# Sampling_Board.net
KiCad netlist of a schematic drawn in Altium Designer
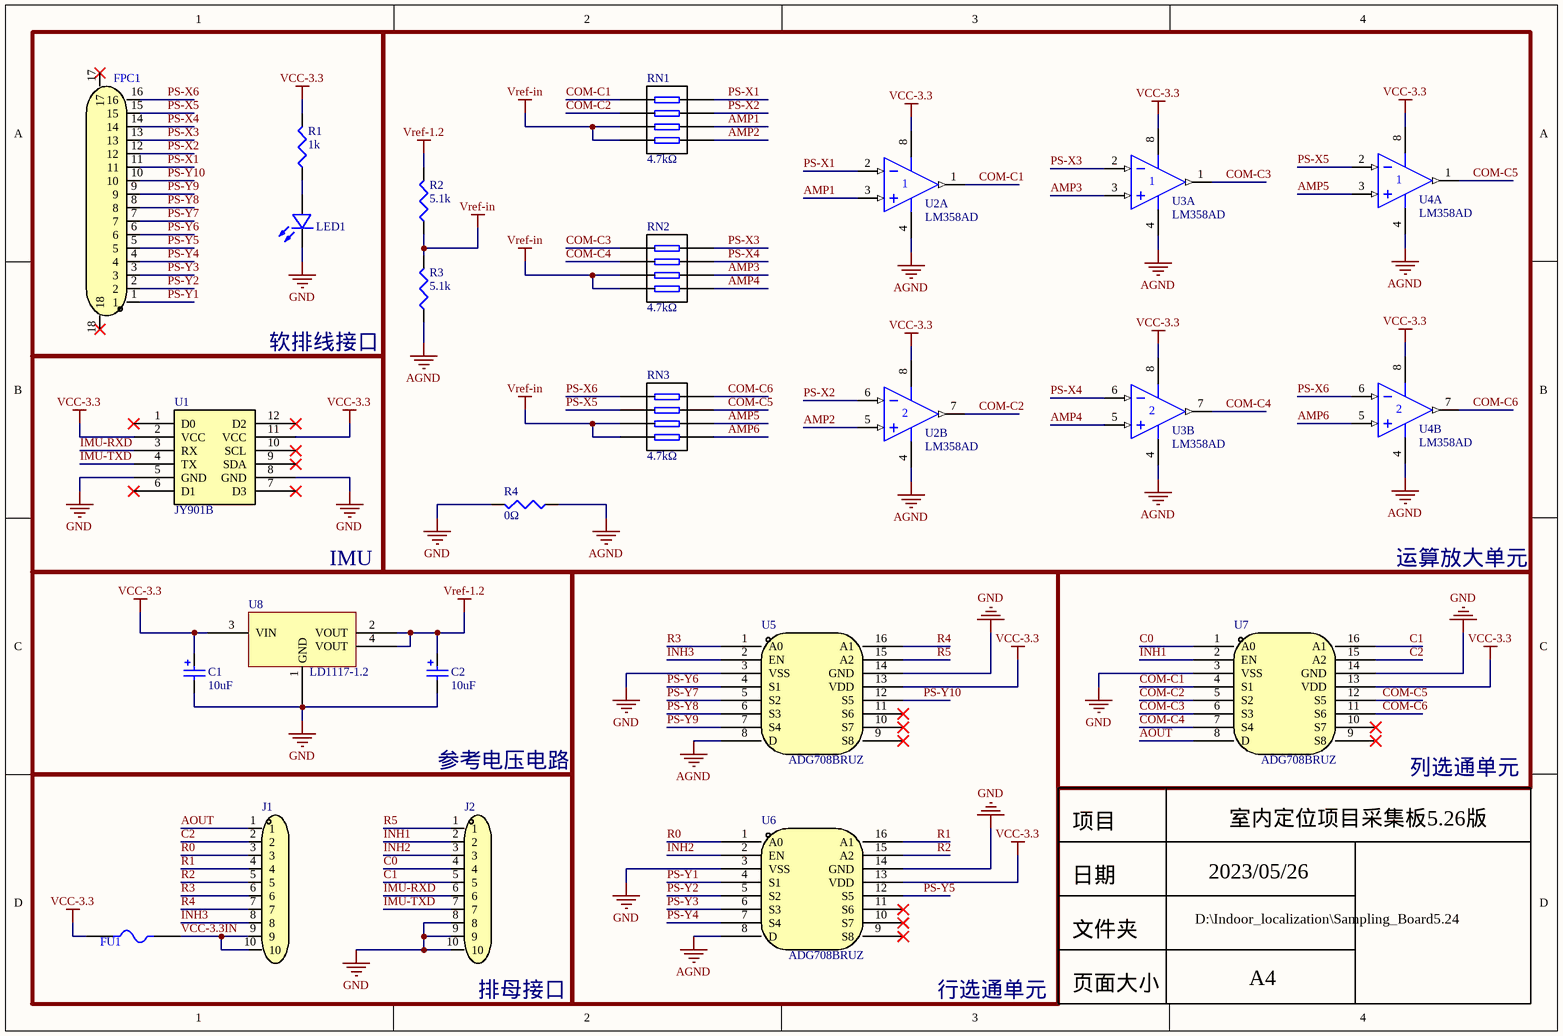
[diagram p0: Sampling_Board.SchDoc]

(export (version "E")
  (design (tool "Eeschema 10.0.6"))
  (components
    (comp (ref "C1")
      (value "10uF")
      (footprint "CAP-SMD_L3.2-W1.6-RD-C7171")
      (description "贴片钽电容")
      (fields (field (name "MANUFACTURER") "Kyocera AVX") (field (name "MANUFACTURER PART") "TAJA106K016RNJ"))
      (libsource (lib "Passive_Device") (part "Cap-TAJA"))
    )
    (comp (ref "C2")
      (value "10uF")
      (footprint "CAP-SMD_L3.2-W1.6-RD-C7171")
      (description "贴片钽电容")
      (fields (field (name "MANUFACTURER") "Kyocera AVX") (field (name "MANUFACTURER PART") "TAJA106K016RNJ"))
      (libsource (lib "Passive_Device") (part "Cap-TAJA"))
    )
    (comp (ref "FPC1")
      (value "1.0K-DX-16PWB")
      (footprint "FPC-SMD_16P-P1.00_HDGC_1.0K-DX-16PWB")
      (description "软排线接口16P")
      (fields (field (name "MANUFACTURER") "HDGC(华德共创)"))
      (libsource (lib "Connector") (part "FPC16P"))
    )
    (comp (ref "FU1")
      (value "FUSE 1A")
      (footprint "F0805")
      (description "贴片保险丝")
      (fields (field (name "MANUFACTURER") "RUILON(瑞隆源)") (field (name "MANUFACTURER PART") "SMD0805P075TF"))
      (libsource (lib "Passive_Device") (part "FU"))
    )
    (comp (ref "J1")
      (value "Header 10X1")
      (footprint "HDR-TH_10P-P2.54_MF254V-11-10-0743")
      (description "10P*1接插件")
      (fields (field (name "DESIGNER") "U?"))
      (libsource (lib "Connector") (part "Header 10X1"))
    )
    (comp (ref "J2")
      (value "Header 10X1")
      (footprint "HDR-TH_10P-P2.54_MF254V-11-10-0743")
      (description "10P*1接插件")
      (fields (field (name "DESIGNER") "U?"))
      (libsource (lib "Connector") (part "Header 10X1"))
    )
    (comp (ref "LED1")
      (value "NCD0603G2")
      (footprint "LED0603-RD")
      (description "LED")
      (fields (field (name "MANUFACTURER") "国星光电"))
      (libsource (lib "Component") (part "NCD0603G2"))
    )
    (comp (ref "R1")
      (value "1k")
      (footprint "R0603")
      (description "Resistor")
      (fields (field (name "PUBLISHER") "Altium Limited"))
      (libsource (lib "Miscellaneous Devices") (part "Res3"))
    )
    (comp (ref "R2")
      (value "5.1k")
      (footprint "R0603")
      (description "Resistor")
      (fields (field (name "PUBLISHER") "Altium Limited"))
      (libsource (lib "Miscellaneous Devices") (part "Res3"))
    )
    (comp (ref "R3")
      (value "5.1k")
      (footprint "R0603")
      (description "Resistor")
      (fields (field (name "PUBLISHER") "Altium Limited"))
      (libsource (lib "Miscellaneous Devices") (part "Res3"))
    )
    (comp (ref "R4")
      (value "0Ω")
      (footprint "R0603")
      (description "Resistor")
      (fields (field (name "PUBLISHER") "Altium Limited"))
      (libsource (lib "Miscellaneous Devices") (part "Res3"))
    )
    (comp (ref "RN1")
      (value "4.7kΩ")
      (footprint "RES-ARRAY-SMD_0603-8P-L3.2-W1.6-BL")
      (description "贴片排阻*4")
      (fields (field (name "MANUFACTURER") "FH(风华)") (field (name "MANUFACTURER PART") "RC-ML08W103JT"))
      (libsource (lib "Passive_Device") (part "Res*4"))
    )
    (comp (ref "RN2")
      (value "4.7kΩ")
      (footprint "RES-ARRAY-SMD_0603-8P-L3.2-W1.6-BL")
      (description "贴片排阻*4")
      (fields (field (name "MANUFACTURER") "FH(风华)") (field (name "MANUFACTURER PART") "RC-ML08W103JT"))
      (libsource (lib "Passive_Device") (part "Res*4"))
    )
    (comp (ref "RN3")
      (value "4.7kΩ")
      (footprint "RES-ARRAY-SMD_0603-8P-L3.2-W1.6-BL")
      (description "贴片排阻*4")
      (fields (field (name "MANUFACTURER") "FH(风华)") (field (name "MANUFACTURER PART") "RC-ML08W103JT"))
      (libsource (lib "Passive_Device") (part "Res*4"))
    )
    (comp (ref "U1")
      (value "JY901B")
      (footprint "JY901B")
      (description "Ten axis inertial sensor")
      (libsource (lib "IMU") (part "JY901B"))
    )
    (comp (ref "U2")
      (value "LM358AD")
      (footprint "D008_L")
      (description "Dual Operational Amplifier")
      (fields (field (name "PUBLISHER") "Altium Limited"))
      (libsource (lib "TI Operational Amplifier") (part "LM358AD"))
    )
    (comp (ref "U3")
      (value "LM358AD")
      (footprint "D008_L")
      (description "Dual Operational Amplifier")
      (fields (field (name "PUBLISHER") "Altium Limited"))
      (libsource (lib "TI Operational Amplifier") (part "LM358AD"))
    )
    (comp (ref "U4")
      (value "LM358AD")
      (footprint "D008_L")
      (description "Dual Operational Amplifier")
      (fields (field (name "PUBLISHER") "Altium Limited"))
      (libsource (lib "TI Operational Amplifier") (part "LM358AD"))
    )
    (comp (ref "U5")
      (value "ADG708BRUZ")
      (footprint "TSSOP-16_L5.0-W4.4-P0.65-LS6.4-BL")
      (description "低电压8通道多路复用器")
      (fields (field (name "MANUFACTURER") "ADI(亚德诺)/LINEAR(凌特)"))
      (libsource (lib "IC_Device") (part "ADG708BRUZ"))
    )
    (comp (ref "U6")
      (value "ADG708BRUZ")
      (footprint "TSSOP-16_L5.0-W4.4-P0.65-LS6.4-BL")
      (description "低电压8通道多路复用器")
      (fields (field (name "MANUFACTURER") "ADI(亚德诺)/LINEAR(凌特)"))
      (libsource (lib "IC_Device") (part "ADG708BRUZ"))
    )
    (comp (ref "U7")
      (value "ADG708BRUZ")
      (footprint "TSSOP-16_L5.0-W4.4-P0.65-LS6.4-BL")
      (description "低电压8通道多路复用器")
      (fields (field (name "MANUFACTURER") "ADI(亚德诺)/LINEAR(凌特)"))
      (libsource (lib "IC_Device") (part "ADG708BRUZ"))
    )
    (comp (ref "U8")
      (value "LD1117-1.2")
      (footprint "SOT-223-3_L6.5-W3.4-P2.30-LS7.0-BR")
      (description "低压差线性稳压器1.2V")
      (libsource (lib "Power") (part "LD1117-1.2"))
    )
  )
  (nets
    (net (code "2") (name "/AMP1") (class "Default")
      (node (ref "RN1") (pin "2") (pinfunction "2_2") (pintype "passive"))
      (node (ref "U2") (pin "3") (pinfunction "IN+_3") (pintype "input"))
    )
    (net (code "3") (name "/AMP2") (class "Default")
      (node (ref "RN1") (pin "1") (pinfunction "1_1") (pintype "passive"))
      (node (ref "U2") (pin "5") (pinfunction "IN+_5") (pintype "input"))
    )
    (net (code "4") (name "/AMP3") (class "Default")
      (node (ref "RN2") (pin "2") (pinfunction "2_2") (pintype "passive"))
      (node (ref "U3") (pin "3") (pinfunction "IN+_3") (pintype "input"))
    )
    (net (code "5") (name "/AMP4") (class "Default")
      (node (ref "RN2") (pin "1") (pinfunction "1_1") (pintype "passive"))
      (node (ref "U3") (pin "5") (pinfunction "IN+_5") (pintype "input"))
    )
    (net (code "6") (name "/AMP5") (class "Default")
      (node (ref "RN3") (pin "2") (pinfunction "2_2") (pintype "passive"))
      (node (ref "U4") (pin "3") (pinfunction "IN+_3") (pintype "input"))
    )
    (net (code "7") (name "/AMP6") (class "Default")
      (node (ref "RN3") (pin "1") (pinfunction "1_1") (pintype "passive"))
      (node (ref "U4") (pin "5") (pinfunction "IN+_5") (pintype "input"))
    )
    (net (code "8") (name "/AOUT") (class "Default")
      (node (ref "J1") (pin "1") (pinfunction "1_1") (pintype "passive"))
      (node (ref "U7") (pin "8") (pinfunction "D_8") (pintype "passive"))
    )
    (net (code "9") (name "/C0") (class "Default")
      (node (ref "J2") (pin "4") (pinfunction "4_4") (pintype "passive"))
      (node (ref "U7") (pin "1") (pinfunction "A0_1") (pintype "passive"))
    )
    (net (code "10") (name "/C1") (class "Default")
      (node (ref "J2") (pin "5") (pinfunction "5_5") (pintype "passive"))
      (node (ref "U7") (pin "16") (pinfunction "A1_16") (pintype "passive"))
    )
    (net (code "11") (name "/C2") (class "Default")
      (node (ref "J1") (pin "2") (pinfunction "2_2") (pintype "passive"))
      (node (ref "U7") (pin "15") (pinfunction "A2_15") (pintype "passive"))
    )
    (net (code "12") (name "/COM-C1") (class "Default")
      (node (ref "RN1") (pin "5") (pinfunction "5_5") (pintype "passive"))
      (node (ref "U2") (pin "1") (pinfunction "OUT_1") (pintype "output"))
      (node (ref "U7") (pin "4") (pinfunction "S1_4") (pintype "passive"))
    )
    (net (code "13") (name "/COM-C2") (class "Default")
      (node (ref "RN1") (pin "6") (pinfunction "6_6") (pintype "passive"))
      (node (ref "U2") (pin "7") (pinfunction "OUT_7") (pintype "output"))
      (node (ref "U7") (pin "5") (pinfunction "S2_5") (pintype "passive"))
    )
    (net (code "14") (name "/COM-C3") (class "Default")
      (node (ref "RN2") (pin "5") (pinfunction "5_5") (pintype "passive"))
      (node (ref "U3") (pin "1") (pinfunction "OUT_1") (pintype "output"))
      (node (ref "U7") (pin "6") (pinfunction "S3_6") (pintype "passive"))
    )
    (net (code "15") (name "/COM-C4") (class "Default")
      (node (ref "RN2") (pin "6") (pinfunction "6_6") (pintype "passive"))
      (node (ref "U3") (pin "7") (pinfunction "OUT_7") (pintype "output"))
      (node (ref "U7") (pin "7") (pinfunction "S4_7") (pintype "passive"))
    )
    (net (code "16") (name "/COM-C5") (class "Default")
      (node (ref "RN3") (pin "3") (pinfunction "3_3") (pintype "passive"))
      (node (ref "U4") (pin "1") (pinfunction "OUT_1") (pintype "output"))
      (node (ref "U7") (pin "12") (pinfunction "S5_12") (pintype "passive"))
    )
    (net (code "17") (name "/COM-C6") (class "Default")
      (node (ref "RN3") (pin "4") (pinfunction "4_4") (pintype "passive"))
      (node (ref "U4") (pin "7") (pinfunction "OUT_7") (pintype "output"))
      (node (ref "U7") (pin "11") (pinfunction "S6_11") (pintype "passive"))
    )
    (net (code "18") (name "/IMU-RXD") (class "Default")
      (node (ref "J2") (pin "6") (pinfunction "6_6") (pintype "passive"))
      (node (ref "U1") (pin "3") (pinfunction "RX_3") (pintype "passive"))
    )
    (net (code "19") (name "/IMU-TXD") (class "Default")
      (node (ref "J2") (pin "7") (pinfunction "7_7") (pintype "passive"))
      (node (ref "U1") (pin "4") (pinfunction "TX_4") (pintype "passive"))
    )
    (net (code "20") (name "/INH1") (class "Default")
      (node (ref "J2") (pin "2") (pinfunction "2_2") (pintype "passive"))
      (node (ref "U7") (pin "2") (pinfunction "EN_2") (pintype "passive"))
    )
    (net (code "21") (name "/INH2") (class "Default")
      (node (ref "J2") (pin "3") (pinfunction "3_3") (pintype "passive"))
      (node (ref "U6") (pin "2") (pinfunction "EN_2") (pintype "passive"))
    )
    (net (code "22") (name "/INH3") (class "Default")
      (node (ref "J1") (pin "8") (pinfunction "8_8") (pintype "passive"))
      (node (ref "U5") (pin "2") (pinfunction "EN_2") (pintype "passive"))
    )
    (net (code "23") (name "/PS-X1") (class "Default")
      (node (ref "FPC1") (pin "11") (pinfunction "11_11") (pintype "passive"))
      (node (ref "RN1") (pin "4") (pinfunction "4_4") (pintype "passive"))
      (node (ref "U2") (pin "2") (pinfunction "IN-_2") (pintype "input"))
    )
    (net (code "24") (name "/PS-X2") (class "Default")
      (node (ref "FPC1") (pin "12") (pinfunction "12_12") (pintype "passive"))
      (node (ref "RN1") (pin "3") (pinfunction "3_3") (pintype "passive"))
      (node (ref "U2") (pin "6") (pinfunction "IN-_6") (pintype "input"))
    )
    (net (code "25") (name "/PS-X3") (class "Default")
      (node (ref "FPC1") (pin "13") (pinfunction "13_13") (pintype "passive"))
      (node (ref "RN2") (pin "4") (pinfunction "4_4") (pintype "passive"))
      (node (ref "U3") (pin "2") (pinfunction "IN-_2") (pintype "input"))
    )
    (net (code "26") (name "/PS-X4") (class "Default")
      (node (ref "FPC1") (pin "14") (pinfunction "14_14") (pintype "passive"))
      (node (ref "RN2") (pin "3") (pinfunction "3_3") (pintype "passive"))
      (node (ref "U3") (pin "6") (pinfunction "IN-_6") (pintype "input"))
    )
    (net (code "27") (name "/PS-X5") (class "Default")
      (node (ref "FPC1") (pin "15") (pinfunction "15_15") (pintype "passive"))
      (node (ref "RN3") (pin "6") (pinfunction "6_6") (pintype "passive"))
      (node (ref "U4") (pin "2") (pinfunction "IN-_2") (pintype "input"))
    )
    (net (code "28") (name "/PS-X6") (class "Default")
      (node (ref "FPC1") (pin "16") (pinfunction "16_16") (pintype "passive"))
      (node (ref "RN3") (pin "5") (pinfunction "5_5") (pintype "passive"))
      (node (ref "U4") (pin "6") (pinfunction "IN-_6") (pintype "input"))
    )
    (net (code "29") (name "/PS-Y1") (class "Default")
      (node (ref "FPC1") (pin "1") (pinfunction "1_1") (pintype "passive"))
      (node (ref "U6") (pin "4") (pinfunction "S1_4") (pintype "passive"))
    )
    (net (code "30") (name "/PS-Y2") (class "Default")
      (node (ref "FPC1") (pin "2") (pinfunction "2_2") (pintype "passive"))
      (node (ref "U6") (pin "5") (pinfunction "S2_5") (pintype "passive"))
    )
    (net (code "31") (name "/PS-Y3") (class "Default")
      (node (ref "FPC1") (pin "3") (pinfunction "3_3") (pintype "passive"))
      (node (ref "U6") (pin "6") (pinfunction "S3_6") (pintype "passive"))
    )
    (net (code "32") (name "/PS-Y4") (class "Default")
      (node (ref "FPC1") (pin "4") (pinfunction "4_4") (pintype "passive"))
      (node (ref "U6") (pin "7") (pinfunction "S4_7") (pintype "passive"))
    )
    (net (code "33") (name "/PS-Y5") (class "Default")
      (node (ref "FPC1") (pin "5") (pinfunction "5_5") (pintype "passive"))
      (node (ref "U6") (pin "12") (pinfunction "S5_12") (pintype "passive"))
    )
    (net (code "34") (name "/PS-Y6") (class "Default")
      (node (ref "FPC1") (pin "6") (pinfunction "6_6") (pintype "passive"))
      (node (ref "U5") (pin "4") (pinfunction "S1_4") (pintype "passive"))
    )
    (net (code "35") (name "/PS-Y7") (class "Default")
      (node (ref "FPC1") (pin "7") (pinfunction "7_7") (pintype "passive"))
      (node (ref "U5") (pin "5") (pinfunction "S2_5") (pintype "passive"))
    )
    (net (code "36") (name "/PS-Y8") (class "Default")
      (node (ref "FPC1") (pin "8") (pinfunction "8_8") (pintype "passive"))
      (node (ref "U5") (pin "6") (pinfunction "S3_6") (pintype "passive"))
    )
    (net (code "37") (name "/PS-Y9") (class "Default")
      (node (ref "FPC1") (pin "9") (pinfunction "9_9") (pintype "passive"))
      (node (ref "U5") (pin "7") (pinfunction "S4_7") (pintype "passive"))
    )
    (net (code "38") (name "/PS-Y10") (class "Default")
      (node (ref "FPC1") (pin "10") (pinfunction "10_10") (pintype "passive"))
      (node (ref "U5") (pin "12") (pinfunction "S5_12") (pintype "passive"))
    )
    (net (code "39") (name "/R0") (class "Default")
      (node (ref "J1") (pin "3") (pinfunction "3_3") (pintype "passive"))
      (node (ref "U6") (pin "1") (pinfunction "A0_1") (pintype "passive"))
    )
    (net (code "40") (name "/R1") (class "Default")
      (node (ref "J1") (pin "4") (pinfunction "4_4") (pintype "passive"))
      (node (ref "U6") (pin "16") (pinfunction "A1_16") (pintype "passive"))
    )
    (net (code "41") (name "/R2") (class "Default")
      (node (ref "J1") (pin "5") (pinfunction "5_5") (pintype "passive"))
      (node (ref "U6") (pin "15") (pinfunction "A2_15") (pintype "passive"))
    )
    (net (code "42") (name "/R3") (class "Default")
      (node (ref "J1") (pin "6") (pinfunction "6_6") (pintype "passive"))
      (node (ref "U5") (pin "1") (pinfunction "A0_1") (pintype "passive"))
    )
    (net (code "43") (name "/R4") (class "Default")
      (node (ref "J1") (pin "7") (pinfunction "7_7") (pintype "passive"))
      (node (ref "U5") (pin "16") (pinfunction "A1_16") (pintype "passive"))
    )
    (net (code "44") (name "/R5") (class "Default")
      (node (ref "J2") (pin "1") (pinfunction "1_1") (pintype "passive"))
      (node (ref "U5") (pin "15") (pinfunction "A2_15") (pintype "passive"))
    )
    (net (code "45") (name "/VCC-3.3IN") (class "Default")
      (node (ref "FU1") (pin "2") (pinfunction "2_2") (pintype "passive"))
      (node (ref "J1") (pin "10") (pinfunction "10_10") (pintype "passive"))
      (node (ref "J1") (pin "9") (pinfunction "9_9") (pintype "passive"))
    )
    (net (code "46") (name "AGND") (class "Default")
      (node (ref "R3") (pin "1") (pinfunction "1_1") (pintype "passive"))
      (node (ref "R4") (pin "1") (pinfunction "1_1") (pintype "passive"))
      (node (ref "U2") (pin "4") (pinfunction "V-_4") (pintype "power_in"))
      (node (ref "U3") (pin "4") (pinfunction "V-_4") (pintype "power_in"))
      (node (ref "U4") (pin "4") (pinfunction "V-_4") (pintype "power_in"))
      (node (ref "U5") (pin "8") (pinfunction "D_8") (pintype "passive"))
      (node (ref "U6") (pin "8") (pinfunction "D_8") (pintype "passive"))
    )
    (net (code "47") (name "GND") (class "Default")
      (node (ref "C1") (pin "2") (pinfunction "2_2") (pintype "passive"))
      (node (ref "C2") (pin "2") (pinfunction "2_2") (pintype "passive"))
      (node (ref "J2") (pin "10") (pinfunction "10_10") (pintype "passive"))
      (node (ref "J2") (pin "8") (pinfunction "8_8") (pintype "passive"))
      (node (ref "J2") (pin "9") (pinfunction "9_9") (pintype "passive"))
      (node (ref "LED1") (pin "1") (pinfunction "K_1") (pintype "passive"))
      (node (ref "R4") (pin "2") (pinfunction "2_2") (pintype "passive"))
      (node (ref "U1") (pin "5") (pinfunction "GND_5") (pintype "passive"))
      (node (ref "U1") (pin "8") (pinfunction "GND_8") (pintype "passive"))
      (node (ref "U5") (pin "14") (pinfunction "GND_14") (pintype "passive"))
      (node (ref "U5") (pin "3") (pinfunction "VSS_3") (pintype "passive"))
      (node (ref "U6") (pin "14") (pinfunction "GND_14") (pintype "passive"))
      (node (ref "U6") (pin "3") (pinfunction "VSS_3") (pintype "passive"))
      (node (ref "U7") (pin "14") (pinfunction "GND_14") (pintype "passive"))
      (node (ref "U7") (pin "3") (pinfunction "VSS_3") (pintype "passive"))
      (node (ref "U8") (pin "1") (pinfunction "GND_1") (pintype "passive"))
    )
    (net (code "48") (name "Net-(LED1-A)") (class "Default")
      (node (ref "LED1") (pin "2") (pinfunction "A_2") (pintype "passive"))
      (node (ref "R1") (pin "1") (pinfunction "1_1") (pintype "passive"))
    )
    (net (code "49") (name "VCC-3.3") (class "Default")
      (node (ref "C1") (pin "1") (pinfunction "1_1") (pintype "passive"))
      (node (ref "FU1") (pin "1") (pinfunction "1_1") (pintype "passive"))
      (node (ref "R1") (pin "2") (pinfunction "2_2") (pintype "passive"))
      (node (ref "U1") (pin "11") (pinfunction "VCC_11") (pintype "passive"))
      (node (ref "U1") (pin "2") (pinfunction "VCC_2") (pintype "passive"))
      (node (ref "U2") (pin "8") (pinfunction "V+_8") (pintype "power_in"))
      (node (ref "U3") (pin "8") (pinfunction "V+_8") (pintype "power_in"))
      (node (ref "U4") (pin "8") (pinfunction "V+_8") (pintype "power_in"))
      (node (ref "U5") (pin "13") (pinfunction "VDD_13") (pintype "passive"))
      (node (ref "U6") (pin "13") (pinfunction "VDD_13") (pintype "passive"))
      (node (ref "U7") (pin "13") (pinfunction "VDD_13") (pintype "passive"))
      (node (ref "U8") (pin "3") (pinfunction "VIN_3") (pintype "passive"))
    )
    (net (code "50") (name "Vref-1.2") (class "Default")
      (node (ref "C2") (pin "1") (pinfunction "1_1") (pintype "passive"))
      (node (ref "R2") (pin "2") (pinfunction "2_2") (pintype "passive"))
      (node (ref "U8") (pin "2") (pinfunction "VOUT_2") (pintype "passive"))
      (node (ref "U8") (pin "4") (pinfunction "VOUT_4") (pintype "passive"))
    )
    (net (code "51") (name "Vref-in") (class "Default")
      (node (ref "R2") (pin "1") (pinfunction "1_1") (pintype "passive"))
      (node (ref "R3") (pin "2") (pinfunction "2_2") (pintype "passive"))
      (node (ref "RN1") (pin "7") (pinfunction "7_7") (pintype "passive"))
      (node (ref "RN1") (pin "8") (pinfunction "8_8") (pintype "passive"))
      (node (ref "RN2") (pin "7") (pinfunction "7_7") (pintype "passive"))
      (node (ref "RN2") (pin "8") (pinfunction "8_8") (pintype "passive"))
      (node (ref "RN3") (pin "7") (pinfunction "7_7") (pintype "passive"))
      (node (ref "RN3") (pin "8") (pinfunction "8_8") (pintype "passive"))
    )
    (net (code "52") (name "unconnected-(FPC1-Pad17)") (class "Default")
      (node (ref "FPC1") (pin "17") (pinfunction "17_17") (pintype "passive+no_connect"))
    )
    (net (code "53") (name "unconnected-(FPC1-Pad18)") (class "Default")
      (node (ref "FPC1") (pin "18") (pinfunction "18_18") (pintype "passive+no_connect"))
    )
    (net (code "54") (name "unconnected-(U1-D0-Pad1)") (class "Default")
      (node (ref "U1") (pin "1") (pinfunction "D0_1") (pintype "passive+no_connect"))
    )
    (net (code "55") (name "unconnected-(U1-D1-Pad6)") (class "Default")
      (node (ref "U1") (pin "6") (pinfunction "D1_6") (pintype "passive+no_connect"))
    )
    (net (code "56") (name "unconnected-(U1-D2-Pad12)") (class "Default")
      (node (ref "U1") (pin "12") (pinfunction "D2_12") (pintype "passive+no_connect"))
    )
    (net (code "57") (name "unconnected-(U1-D3-Pad7)") (class "Default")
      (node (ref "U1") (pin "7") (pinfunction "D3_7") (pintype "passive+no_connect"))
    )
    (net (code "58") (name "unconnected-(U1-SCL-Pad10)") (class "Default")
      (node (ref "U1") (pin "10") (pinfunction "SCL_10") (pintype "passive+no_connect"))
    )
    (net (code "59") (name "unconnected-(U1-SDA-Pad9)") (class "Default")
      (node (ref "U1") (pin "9") (pinfunction "SDA_9") (pintype "passive+no_connect"))
    )
    (net (code "60") (name "unconnected-(U5-S6-Pad11)") (class "Default")
      (node (ref "U5") (pin "11") (pinfunction "S6_11") (pintype "passive+no_connect"))
    )
    (net (code "61") (name "unconnected-(U5-S7-Pad10)") (class "Default")
      (node (ref "U5") (pin "10") (pinfunction "S7_10") (pintype "passive+no_connect"))
    )
    (net (code "62") (name "unconnected-(U5-S8-Pad9)") (class "Default")
      (node (ref "U5") (pin "9") (pinfunction "S8_9") (pintype "passive+no_connect"))
    )
    (net (code "63") (name "unconnected-(U6-S6-Pad11)") (class "Default")
      (node (ref "U6") (pin "11") (pinfunction "S6_11") (pintype "passive+no_connect"))
    )
    (net (code "64") (name "unconnected-(U6-S7-Pad10)") (class "Default")
      (node (ref "U6") (pin "10") (pinfunction "S7_10") (pintype "passive+no_connect"))
    )
    (net (code "65") (name "unconnected-(U6-S8-Pad9)") (class "Default")
      (node (ref "U6") (pin "9") (pinfunction "S8_9") (pintype "passive+no_connect"))
    )
    (net (code "66") (name "unconnected-(U7-S7-Pad10)") (class "Default")
      (node (ref "U7") (pin "10") (pinfunction "S7_10") (pintype "passive+no_connect"))
    )
    (net (code "67") (name "unconnected-(U7-S8-Pad9)") (class "Default")
      (node (ref "U7") (pin "9") (pinfunction "S8_9") (pintype "passive+no_connect"))
    )
  )
)
